# General_design.net
KiCad netlist of a schematic drawn in Altium Designer
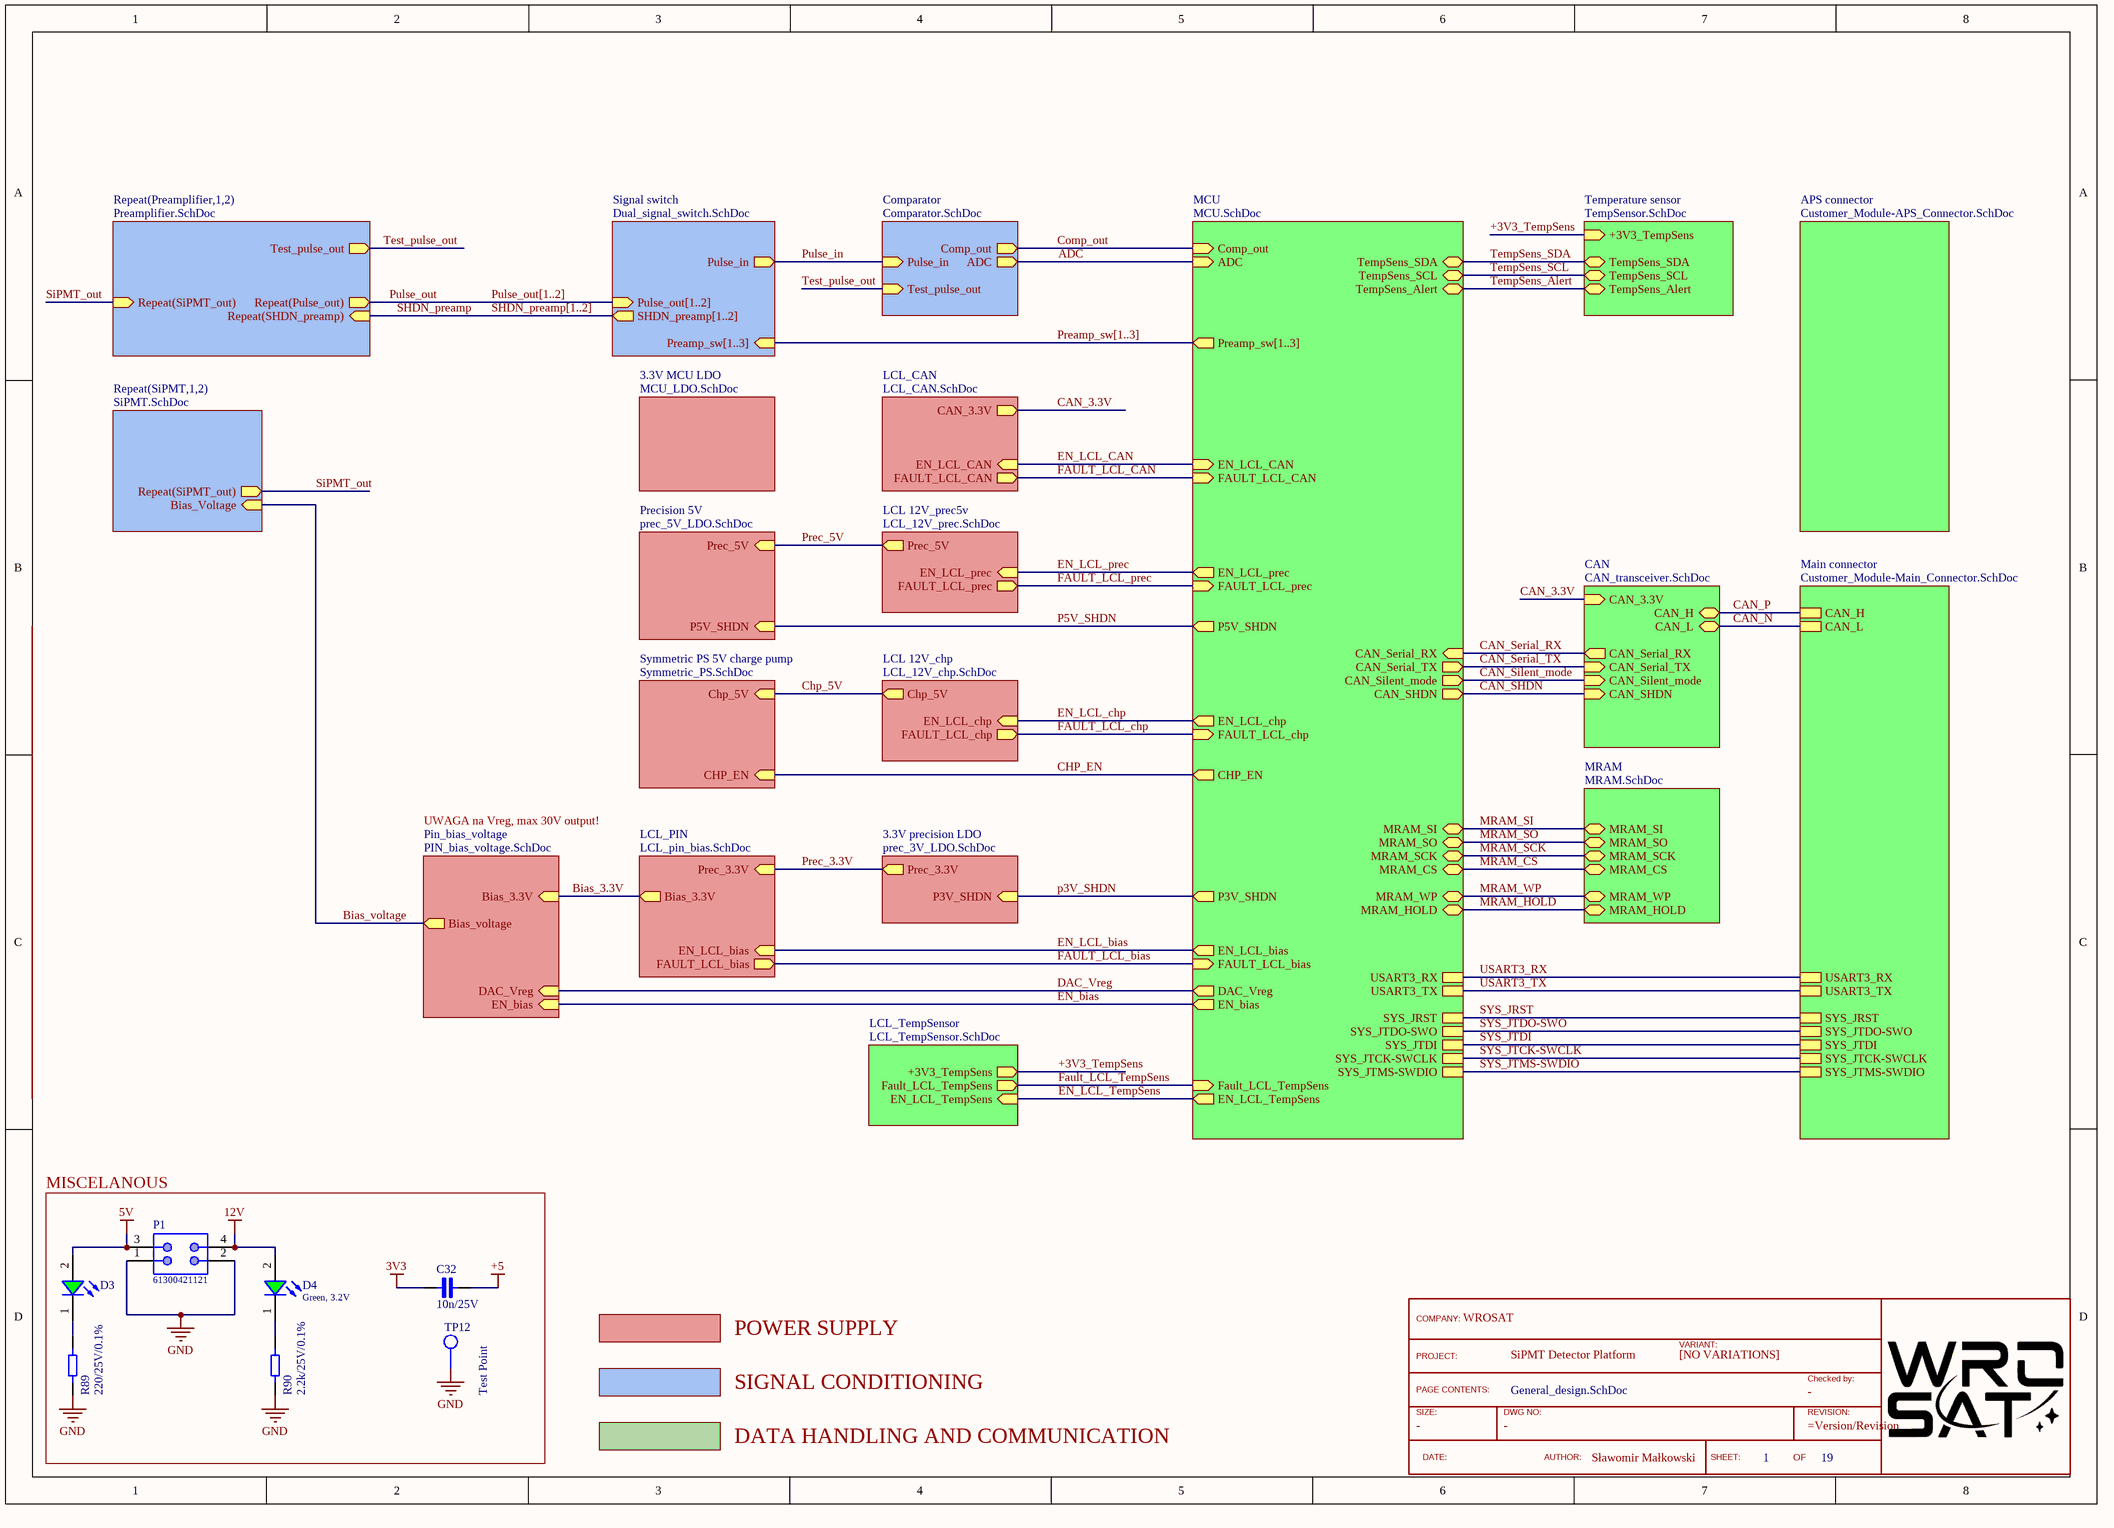
[diagram p0: General_design.SchDoc]

(export (version "E")
  (design (tool "Eeschema 10.0.6"))
  (components
    (comp (ref "C32")
      (value "10n/25V")
      (footprint "Cap_0402")
      (description "Ceramic Capacitor 10n / 0402 / 25V / ±5%, Wurth Elektronik MLCC")
      (libsource (lib "Cubesat_lib") (part "Cap_0402_10n"))
    )
    (comp (ref "D3")
      (value "Green, 3.2V")
      (footprint "WL-SMCW_0603_H=0.7mm")
      (description "WL-SMCW SMT Mono-color Chip LED Waterclear, size 0603, Green, 3.2V, 140deg")
      (fields (field (name "PART NUMBER") "150060GS75000") (field (name "PUBLISHER") "Wurth Elektronik"))
      (libsource (lib "LEDS") (part "150060GS75000"))
    )
    (comp (ref "D4")
      (value "Green, 3.2V")
      (footprint "WL-SMCW_0603_H=0.7mm")
      (description "WL-SMCW SMT Mono-color Chip LED Waterclear, size 0603, Green, 3.2V, 140deg")
      (fields (field (name "PART NUMBER") "150060GS75000") (field (name "PUBLISHER") "Wurth Elektronik"))
      (libsource (lib "LEDS") (part "150060GS75000"))
    )
    (comp (ref "P1")
      (value "61300421121")
      (footprint "61300421121")
      (description "WR-PHD Pin Header, THT, pitch 2.54mm, Dual Row, Vertical, 4p")
      (fields (field (name "MANUFACTURER") "Wurth Elektronik"))
      (libsource (lib "goldpin") (part "61300421121"))
    )
    (comp (ref "R89")
      (value "220/25V/0.1%")
      (footprint "RES_0402")
      (description "Vishay, thin film resistor 1/25V/0.1%")
      (libsource (lib "Cubesat_lib") (part "Res_0402_1"))
    )
    (comp (ref "R90")
      (value "2.2k/25V/0.1%")
      (footprint "RES_0402")
      (description "Vishay, thin film resistor 2.2k/25V/0.1%")
      (libsource (lib "Cubesat_lib") (part "Res_0402_1"))
    )
    (comp (ref "TP12")
      (value "Test Point")
      (footprint "Test Point SMT")
      (libsource (lib "Cubesat_lib") (part "Test Point"))
    )
  )
  (nets
    (net (code "4") (name "+5") (class "Default")
      (node (ref "C32") (pin "2") (pinfunction "2_2") (pintype "passive"))
    )
    (net (code "57") (name "3V3") (class "Default")
      (node (ref "C32") (pin "1") (pinfunction "1_1") (pintype "passive"))
    )
    (net (code "58") (name "5V") (class "Default")
      (node (ref "D3") (pin "2") (pinfunction "A_2") (pintype "passive"))
      (node (ref "P1") (pin "3") (pinfunction "3_3") (pintype "passive"))
    )
    (net (code "59") (name "12V") (class "Default")
      (node (ref "D4") (pin "2") (pinfunction "A_2") (pintype "passive"))
      (node (ref "P1") (pin "4") (pinfunction "4_4") (pintype "passive"))
    )
    (net (code "60") (name "GND") (class "Default")
      (node (ref "P1") (pin "1") (pinfunction "1_1") (pintype "passive"))
      (node (ref "P1") (pin "2") (pinfunction "2_2") (pintype "passive"))
      (node (ref "R89") (pin "1") (pinfunction "1_1") (pintype "passive"))
      (node (ref "R90") (pin "1") (pinfunction "1_1") (pintype "passive"))
      (node (ref "TP12") (pin "1") (pinfunction "1_1") (pintype "passive"))
    )
    (net (code "61") (name "Net-(D3-K)") (class "Default")
      (node (ref "D3") (pin "1") (pinfunction "K_1") (pintype "passive"))
      (node (ref "R89") (pin "2") (pinfunction "2_2") (pintype "passive"))
    )
    (net (code "62") (name "Net-(D4-K)") (class "Default")
      (node (ref "D4") (pin "1") (pinfunction "K_1") (pintype "passive"))
      (node (ref "R90") (pin "2") (pinfunction "2_2") (pintype "passive"))
    )
  )
)
